# Kasli-SOC_bank0.net
KiCad netlist of a schematic drawn in Altium Designer
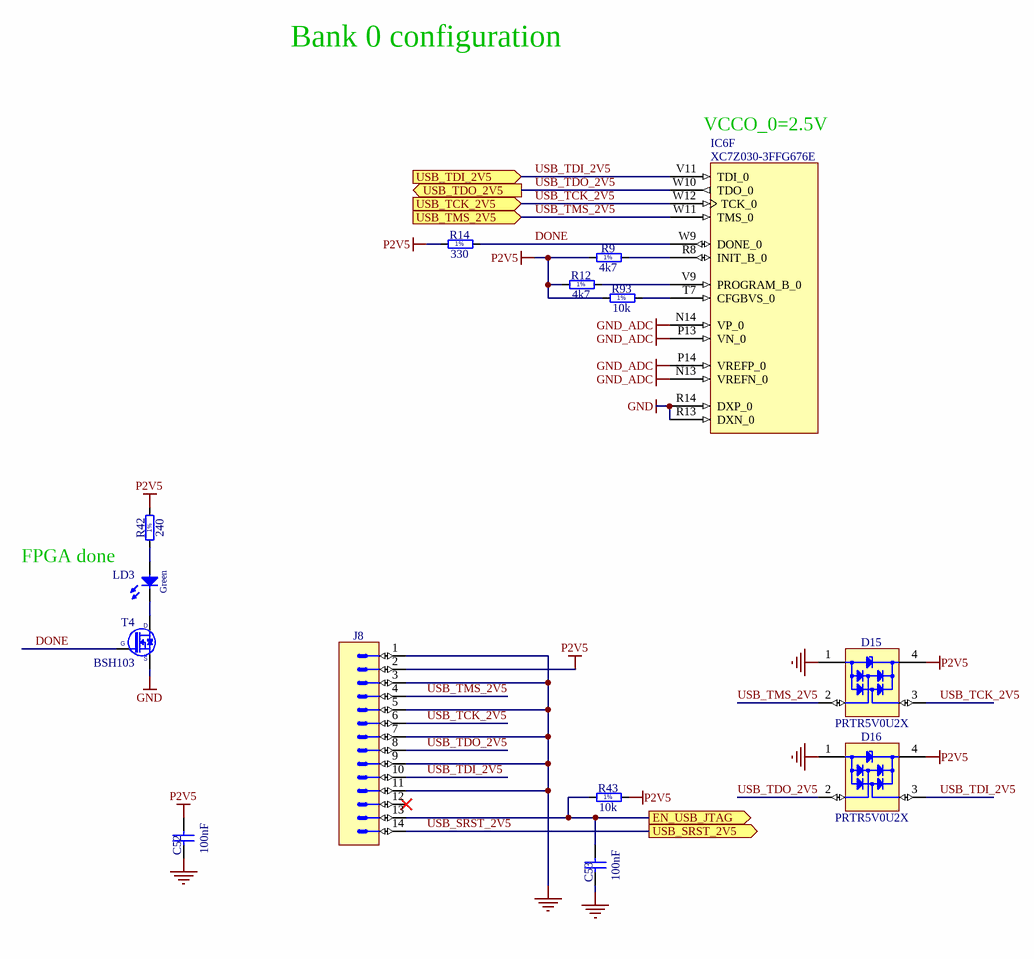
[diagram p0: Kasli-SOC_bank0.SchDoc]

(export (version "E")
  (design (tool "Eeschema 10.0.6"))
  (components
    (comp (ref "C52")
      (value "100nF")
      (footprint "CAPC1005X55N")
      (description "Non-polarised capacitor")
      (fields
        (field (name "PART NUMBER") "CC0402_100NF_16V_10%_X7R")
        (field (name "VOLTAGE") "16V")
        (field (name "AUTHOR") "CERN DEM JLC")
      )
      (libsource (lib "Capacitors") (part "Capacitor - non polarized"))
    )
    (comp (ref "C53")
      (value "100nF")
      (footprint "CAPC1005X55N")
      (description "Non-polarised capacitor")
      (fields
        (field (name "PART NUMBER") "CC0402_100NF_16V_10%_X7R")
        (field (name "VOLTAGE") "16V")
        (field (name "AUTHOR") "CERN DEM JLC")
      )
      (libsource (lib "Capacitors") (part "Capacitor - non polarized"))
    )
    (comp (ref "D15")
      (value "PRTR5V0U2X")
      (footprint "SOT190P230X110-4N")
      (description "Ultra Low Capacitance Double Rail-to-Rail ESD Protection Diode")
      (fields
        (field (name "VOLTAGE") "5.5V")
        (field (name "MANUFACTURER") "NXP SEMICONDUCTORS")
        (field (name "AUTHOR") "CERN DEM JLC")
      )
      (libsource (lib "ICs And Semiconductors") (part "PRTR5V0U2X"))
    )
    (comp (ref "D16")
      (value "PRTR5V0U2X")
      (footprint "SOT190P230X110-4N")
      (description "Ultra Low Capacitance Double Rail-to-Rail ESD Protection Diode")
      (fields
        (field (name "VOLTAGE") "5.5V")
        (field (name "MANUFACTURER") "NXP SEMICONDUCTORS")
        (field (name "AUTHOR") "CERN DEM JLC")
      )
      (libsource (lib "ICs And Semiconductors") (part "PRTR5V0U2X"))
    )
    (comp (ref "IC6")
      (value "XC7Z030-3FFG676E")
      (footprint "BGA676C100P26X26_2700X2700X324")
      (fields
        (field (name "MANUFACTURER") "XILINX")
        (field (name "MANUFACTURER PART NUMBER") "XC7Z030-2FFG676I")
        (field (name "AUTHOR") "CERN DEM JLC")
      )
      (libsource (lib "ICs And Semiconductors") (part "XC7Z030-2FFG676I"))
    )
    (comp (ref "J8")
      (value "Milli-Grid™")
      (footprint "MOLEX_87832-1420")
      (description "Connector 14 Male")
      (fields
        (field (name "PART NUMBER") "MOLEX_87832-1420")
        (field (name "MANUFACTURER") "MOLEX")
        (field (name "AUTHOR") "CERN DEM JLC")
      )
      (libsource (lib "Connectors") (part "Connector 14 Male"))
    )
    (comp (ref "LD3")
      (value "Green")
      (footprint "LED_KINGBRIGHT_KPH-1608CGCK")
      (description "LED Green 1C 2A")
      (fields
        (field (name "MANUFACTURER PART NUMBER") "KPH-1608CGCK")
        (field (name "PART NUMBER") "LED_KINGBRIGHT_KPH-1608CGCK")
        (field (name "AUTHOR") "CERN DEM JLC")
      )
      (libsource (lib "ICs And Semiconductors") (part "LED Green 1C 2A"))
    )
    (comp (ref "R9")
      (value "4k7")
      (footprint "RESC1005X40N")
      (description "Resistor - 1%")
      (fields
        (field (name "PART NUMBER") "R0402_4K7_1%_0.0625W_100PPM")
        (field (name "POWER") "0.0625W")
        (field (name "AUTHOR") "CERN DEM JLC")
      )
      (libsource (lib "Resistors") (part "Resistor - 1%"))
    )
    (comp (ref "R12")
      (value "4k7")
      (footprint "RESC1005X40N")
      (description "Resistor - 1%")
      (fields
        (field (name "PART NUMBER") "R0402_4K7_1%_0.0625W_100PPM")
        (field (name "POWER") "0.0625W")
        (field (name "AUTHOR") "CERN DEM JLC")
      )
      (libsource (lib "Resistors") (part "Resistor - 1%"))
    )
    (comp (ref "R14")
      (value "330")
      (footprint "RESC1005X40N")
      (description "Resistor - 1%")
      (fields
        (field (name "PART NUMBER") "R0402_330R_1%_0.0625W_100PPM")
        (field (name "POWER") "0.0625W")
        (field (name "AUTHOR") "CERN DEM JLC")
      )
      (libsource (lib "Resistors") (part "Resistor - 1%"))
    )
    (comp (ref "R42")
      (value "240")
      (footprint "RESC1005X40N")
      (description "Resistor - 1%")
      (fields
        (field (name "PART NUMBER") "R0402_240R_1%_0.0625W_100PPM")
        (field (name "POWER") "0.0625W")
        (field (name "AUTHOR") "CERN DEM JLC")
      )
      (libsource (lib "Resistors") (part "Resistor - 1%"))
    )
    (comp (ref "R43")
      (value "10k")
      (footprint "RESC1005X40N")
      (description "Resistor - 1%")
      (fields
        (field (name "PART NUMBER") "R0402_10K_1%_0.0625W_100PPM")
        (field (name "POWER") "0.0625W")
        (field (name "AUTHOR") "CERN DEM JLC")
      )
      (libsource (lib "Resistors") (part "Resistor - 1%"))
    )
    (comp (ref "R93")
      (value "10k")
      (footprint "RESC1005X40N")
      (description "Resistor - 1%")
      (fields
        (field (name "PART NUMBER") "R0402_10K_1%_0.0625W_100PPM")
        (field (name "POWER") "0.0625W")
        (field (name "AUTHOR") "CERN DEM JLC")
      )
      (libsource (lib "Resistors") (part "Resistor - 1%"))
    )
    (comp (ref "T4")
      (value "BSH103")
      (footprint "SOT95P230X110-3N")
      (description "N-CHANNEL MOSFET WITH DIODE")
      (fields (field (name "MANUFACTURER") "NEXPERIA") (field (name "AUTHOR") "CERN DEM JLC"))
      (libsource (lib "ICs And Semiconductors") (part "N-MOSFET-D 1G 2S 3D"))
    )
  )
  (nets
    (net (code "1") (name "/DONE") (class "Default")
      (node (ref "IC6") (pin "W9") (pinfunction "DONE_0_W9") (pintype "bidirectional"))
      (node (ref "R14") (pin "2") (pinfunction "2_2") (pintype "passive"))
      (node (ref "T4") (pin "1") (pinfunction "G_1") (pintype "passive"))
    )
    (net (code "2") (name "/EN_USB_JTAG") (class "Default")
      (node (ref "C53") (pin "2") (pinfunction "2_2") (pintype "passive"))
      (node (ref "J8") (pin "13") (pinfunction "13_13") (pintype "bidirectional"))
      (node (ref "R43") (pin "1") (pinfunction "1_1") (pintype "passive"))
    )
    (net (code "3") (name "/USB_SRST_2V5") (class "Default")
      (node (ref "J8") (pin "14") (pinfunction "14_14") (pintype "bidirectional"))
    )
    (net (code "4") (name "/USB_TCK_2V5") (class "Default")
      (node (ref "D15") (pin "3") (pinfunction "I/O2_3") (pintype "bidirectional"))
      (node (ref "IC6") (pin "W12") (pinfunction "TCK_0_W12") (pintype "input"))
      (node (ref "J8") (pin "6") (pinfunction "6_6") (pintype "bidirectional"))
    )
    (net (code "5") (name "/USB_TDI_2V5") (class "Default")
      (node (ref "D16") (pin "3") (pinfunction "I/O2_3") (pintype "bidirectional"))
      (node (ref "IC6") (pin "V11") (pinfunction "TDI_0_V11") (pintype "input"))
      (node (ref "J8") (pin "10") (pinfunction "10_10") (pintype "bidirectional"))
    )
    (net (code "6") (name "/USB_TDO_2V5") (class "Default")
      (node (ref "D16") (pin "2") (pinfunction "I/O1_2") (pintype "bidirectional"))
      (node (ref "IC6") (pin "W10") (pinfunction "TDO_0_W10") (pintype "output"))
      (node (ref "J8") (pin "8") (pinfunction "8_8") (pintype "bidirectional"))
    )
    (net (code "7") (name "/USB_TMS_2V5") (class "Default")
      (node (ref "D15") (pin "2") (pinfunction "I/O1_2") (pintype "bidirectional"))
      (node (ref "IC6") (pin "W11") (pinfunction "TMS_0_W11") (pintype "input"))
      (node (ref "J8") (pin "4") (pinfunction "4_4") (pintype "bidirectional"))
    )
    (net (code "8") (name "GND") (class "Default")
      (node (ref "C52") (pin "1") (pinfunction "1_1") (pintype "passive"))
      (node (ref "C53") (pin "1") (pinfunction "1_1") (pintype "passive"))
      (node (ref "D15") (pin "1") (pinfunction "GND_1") (pintype "power_in"))
      (node (ref "D16") (pin "1") (pinfunction "GND_1") (pintype "power_in"))
      (node (ref "IC6") (pin "R13") (pinfunction "DXN_0_R13") (pintype "input"))
      (node (ref "IC6") (pin "R14") (pinfunction "DXP_0_R14") (pintype "input"))
      (node (ref "J8") (pin "1") (pinfunction "1_1") (pintype "bidirectional"))
      (node (ref "J8") (pin "11") (pinfunction "11_11") (pintype "bidirectional"))
      (node (ref "J8") (pin "3") (pinfunction "3_3") (pintype "bidirectional"))
      (node (ref "J8") (pin "5") (pinfunction "5_5") (pintype "bidirectional"))
      (node (ref "J8") (pin "7") (pinfunction "7_7") (pintype "bidirectional"))
      (node (ref "J8") (pin "9") (pinfunction "9_9") (pintype "bidirectional"))
      (node (ref "T4") (pin "2") (pinfunction "S_2") (pintype "passive"))
    )
    (net (code "9") (name "GND_ADC") (class "Default")
      (node (ref "IC6") (pin "N13") (pinfunction "VREFN_0_N13") (pintype "input"))
      (node (ref "IC6") (pin "N14") (pinfunction "VP_0_N14") (pintype "input"))
      (node (ref "IC6") (pin "P13") (pinfunction "VN_0_P13") (pintype "input"))
      (node (ref "IC6") (pin "P14") (pinfunction "VREFP_0_P14") (pintype "input"))
    )
    (net (code "10") (name "Net-(IC6F-CFGBVS_0)") (class "Default")
      (node (ref "IC6") (pin "T7") (pinfunction "CFGBVS_0_T7") (pintype "input"))
      (node (ref "R93") (pin "2") (pinfunction "2_2") (pintype "passive"))
    )
    (net (code "11") (name "Net-(IC6F-INIT_B_0)") (class "Default")
      (node (ref "IC6") (pin "R8") (pinfunction "INIT_B_0_R8") (pintype "bidirectional"))
      (node (ref "R9") (pin "2") (pinfunction "2_2") (pintype "passive"))
    )
    (net (code "12") (name "Net-(IC6F-PROGRAM_B_0)") (class "Default")
      (node (ref "IC6") (pin "V9") (pinfunction "PROGRAM_B_0_V9") (pintype "input"))
      (node (ref "R12") (pin "2") (pinfunction "2_2") (pintype "passive"))
    )
    (net (code "13") (name "Net-(LD3-A)") (class "Default")
      (node (ref "LD3") (pin "2") (pinfunction "A_2") (pintype "passive"))
      (node (ref "R42") (pin "1") (pinfunction "1_1") (pintype "passive"))
    )
    (net (code "14") (name "Net-(LD3-C)") (class "Default")
      (node (ref "LD3") (pin "1") (pinfunction "C_1") (pintype "passive"))
      (node (ref "T4") (pin "3") (pinfunction "D_3") (pintype "passive"))
    )
    (net (code "15") (name "P2V5") (class "Default")
      (node (ref "C52") (pin "2") (pinfunction "2_2") (pintype "passive"))
      (node (ref "D15") (pin "4") (pinfunction "VCC_4") (pintype "power_in"))
      (node (ref "D16") (pin "4") (pinfunction "VCC_4") (pintype "power_in"))
      (node (ref "J8") (pin "2") (pinfunction "2_2") (pintype "bidirectional"))
      (node (ref "R12") (pin "1") (pinfunction "1_1") (pintype "passive"))
      (node (ref "R14") (pin "1") (pinfunction "1_1") (pintype "passive"))
      (node (ref "R42") (pin "2") (pinfunction "2_2") (pintype "passive"))
      (node (ref "R43") (pin "2") (pinfunction "2_2") (pintype "passive"))
      (node (ref "R9") (pin "1") (pinfunction "1_1") (pintype "passive"))
      (node (ref "R93") (pin "1") (pinfunction "1_1") (pintype "passive"))
    )
    (net (code "16") (name "unconnected-(J8-Pad12)") (class "Default")
      (node (ref "J8") (pin "12") (pinfunction "12_12") (pintype "bidirectional+no_connect"))
    )
  )
)
